# Sheet2.net
KiCad netlist of a schematic drawn in Altium Designer
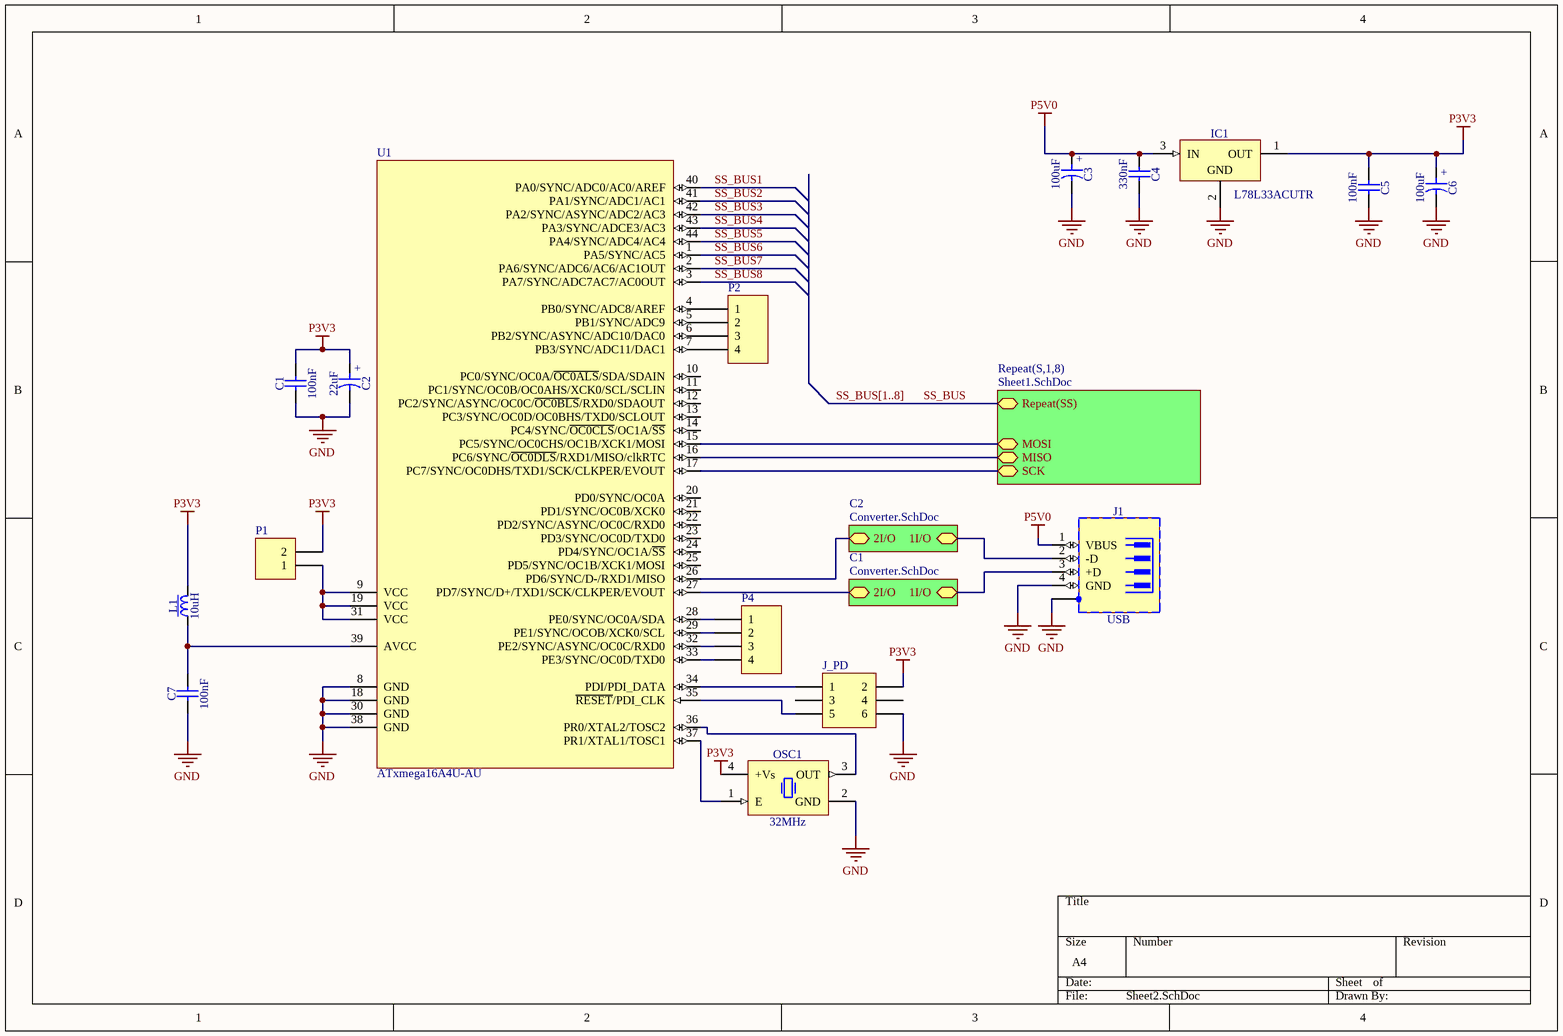
[diagram p0: Sheet2.SchDoc]

(export (version "E")
  (design (tool "Eeschema 10.0.6"))
  (components
    (comp (ref "C1")
      (value "100nF")
      (footprint "CAPC2012X135N")
      (description "Non-polarised capacitor")
      (fields
        (field (name "PART NUMBER") "CC0805_100NF_50V_10%_X7R")
        (field (name "VOLTAGE") "50V")
        (field (name "AUTHOR") "CERN DEM JLC")
      )
      (libsource (lib "Capacitors") (part "Capacitor - non polarized"))
    )
    (comp (ref "C2")
      (value "22uF")
      (footprint "CAPAE430X540N")
      (description "Polarised capacitor")
      (fields
        (field (name "PART NUMBER") "CAE430-540_22UF_10V_20%")
        (field (name "VOLTAGE") "10V")
        (field (name "AUTHOR") "CERN DEM JLC")
      )
      (libsource (lib "Capacitors") (part "Capacitor - polarized"))
    )
    (comp (ref "C3")
      (value "100uF")
      (footprint "CAPAE660X540N")
      (description "Polarised capacitor")
      (fields
        (field (name "PART NUMBER") "CAE660-540_100UF_6.3V_20%")
        (field (name "VOLTAGE") "6.3V")
        (field (name "AUTHOR") "CERN DEM JLC")
      )
      (libsource (lib "Capacitors") (part "Capacitor - polarized"))
    )
    (comp (ref "C4")
      (value "330nF")
      (footprint "CAPC2012X135N")
      (description "Non-polarised capacitor")
      (fields
        (field (name "PART NUMBER") "CC0805_330NF_16V_10%_X7R")
        (field (name "VOLTAGE") "16V")
        (field (name "AUTHOR") "CERN DEM JLC")
      )
      (libsource (lib "Capacitors") (part "Capacitor - non polarized"))
    )
    (comp (ref "C5")
      (value "100nF")
      (footprint "CAPC2012X135N")
      (description "Non-polarised capacitor")
      (fields
        (field (name "PART NUMBER") "CC0805_100NF_50V_10%_X7R")
        (field (name "VOLTAGE") "50V")
        (field (name "AUTHOR") "CERN DEM JLC")
      )
      (libsource (lib "Capacitors") (part "Capacitor - non polarized"))
    )
    (comp (ref "C6")
      (value "100uF")
      (footprint "CAPAE660X540N")
      (description "Polarised capacitor")
      (fields
        (field (name "PART NUMBER") "CAE660-540_100UF_6.3V_20%")
        (field (name "VOLTAGE") "6.3V")
        (field (name "AUTHOR") "CERN DEM JLC")
      )
      (libsource (lib "Capacitors") (part "Capacitor - polarized"))
    )
    (comp (ref "C7")
      (value "100nF")
      (footprint "CAPC2012X135N")
      (description "Non-polarised capacitor")
      (fields
        (field (name "PART NUMBER") "CC0805_100NF_50V_10%_X7R")
        (field (name "VOLTAGE") "50V")
        (field (name "AUTHOR") "CERN DEM JLC")
      )
      (libsource (lib "Capacitors") (part "Capacitor - non polarized"))
    )
    (comp (ref "IC1")
      (value "L78L33ACUTR")
      (footprint "SOT89")
      (description "3-Terminal Regulator 1=OUT 2=GND 3=IN")
      (fields (field (name "MANUFACTURER") "ST MICROELECTRONICS") (field (name "AUTHOR") "CERN DEM JLC"))
      (libsource (lib "ICs And Semiconductors") (part "REG3 1OUT-2GND-3IN"))
    )
    (comp (ref "J1")
      (value "USB")
      (footprint "FCI_87520-0010BLF")
      (description "4 Pin + 1 Shield USB Receptacle")
      (fields
        (field (name "PART NUMBER") "FCI_87520-0010BLF")
        (field (name "MANUFACTURER") "FCI")
        (field (name "AUTHOR") "CERN DEM JMW")
      )
      (libsource (lib "Connectors") (part "Connector USB 4 Pin + 1Shield"))
    )
    (comp (ref "J_PD")
      (value "~")
      (footprint "HDR2X3")
      (description "Header, 3-Pin, Dual row")
      (fields (field (name "PUBLISHER") "Altium Limited"))
      (libsource (lib "Miscellaneous Connectors") (part "Header 3X2"))
    )
    (comp (ref "L1")
      (value "10uH")
      (footprint "IND_MURATA_LQH32")
      (description "Inductor With Core")
      (fields
        (field (name "PART NUMBER") "IND_10UH_10%_MURATA_LQH32CN100K33L")
        (field (name "POWER") "450mA")
        (field (name "AUTHOR") "CERN DEM JLC")
      )
      (libsource (lib "Inductors & Transformers") (part "Inductor With Magnetic core"))
    )
    (comp (ref "OSC1")
      (value "32MHz")
      (footprint "OSC_IQD_CFPS-32")
      (description "Oscillator 4 pins 1=E 2=GND 3=OUT 4=+Vs")
      (fields
        (field (name "PART NUMBER") "OSC_32MHZ_IQD_LFSPXO025916")
        (field (name "MANUFACTURER") "IQD FREQUENCY PRODUCTS")
        (field (name "AUTHOR") "CERN DEM JLC")
      )
      (libsource (lib "ICs And Semiconductors") (part "Oscillator 1E 2GND 3OUT 4Vs"))
    )
    (comp (ref "P1")
      (value "~")
      (footprint "HDR1X2")
      (description "Header, 2-Pin")
      (fields (field (name "PUBLISHER") "Altium Limited"))
      (libsource (lib "Miscellaneous Connectors") (part "Header 2"))
    )
    (comp (ref "P2")
      (value "~")
      (footprint "HDR1X4")
      (description "Header, 4-Pin")
      (fields (field (name "PUBLISHER") "Altium Limited"))
      (libsource (lib "Miscellaneous Connectors") (part "Header 4"))
    )
    (comp (ref "P4")
      (value "~")
      (footprint "HDR1X4")
      (description "Header, 4-Pin")
      (fields (field (name "PUBLISHER") "Altium Limited"))
      (libsource (lib "Miscellaneous Connectors") (part "Header 4"))
    )
    (comp (ref "U1")
      (value "ATxmega16A4U-AU")
      (footprint "44A_N")
      (fields (field (name "PUBLISHER") "Altium Limited"))
      (libsource (lib "RFID_system_atxmegau") (part "ATxmega16A4-AU"))
    )
  )
  (nets
    (net (code "1") (name "/1I{slash}O") (class "Default")
      (node (ref "J1") (pin "3") (pinfunction "+D_3") (pintype "bidirectional"))
    )
    (net (code "2") (name "/1I{slash}O_1") (class "Default")
      (node (ref "J1") (pin "2") (pinfunction "-D_2") (pintype "bidirectional"))
    )
    (net (code "3") (name "/2I{slash}O") (class "Default")
      (node (ref "U1") (pin "27") (pinfunction "PD7/SYNC/D+/TXD1/SCK/CLKPER/EVOUT_27") (pintype "bidirectional"))
    )
    (net (code "4") (name "/2I{slash}O_1") (class "Default")
      (node (ref "U1") (pin "26") (pinfunction "PD6/SYNC/D-/RXD1/MISO_26") (pintype "bidirectional"))
    )
    (net (code "5") (name "/MISO") (class "Default")
      (node (ref "U1") (pin "16") (pinfunction "PC6/SYNC/~{OC0DLS}/RXD1/MISO/clkRTC_16") (pintype "bidirectional"))
    )
    (net (code "6") (name "/MOSI") (class "Default")
      (node (ref "U1") (pin "15") (pinfunction "PC5/SYNC/OC0CHS/OC1B/XCK1/MOSI_15") (pintype "bidirectional"))
    )
    (net (code "7") (name "/SCK") (class "Default")
      (node (ref "U1") (pin "17") (pinfunction "PC7/SYNC/OC0DHS/TXD1/SCK/CLKPER/EVOUT_17") (pintype "bidirectional"))
    )
    (net (code "9") (name "/SS_BUS1") (class "Default")
      (node (ref "U1") (pin "40") (pinfunction "PA0/SYNC/ADC0/AC0/AREF_40") (pintype "bidirectional"))
    )
    (net (code "10") (name "/SS_BUS2") (class "Default")
      (node (ref "U1") (pin "41") (pinfunction "PA1/SYNC/ADC1/AC1_41") (pintype "bidirectional"))
    )
    (net (code "11") (name "/SS_BUS3") (class "Default")
      (node (ref "U1") (pin "42") (pinfunction "PA2/SYNC/ASYNC/ADC2/AC3_42") (pintype "bidirectional"))
    )
    (net (code "12") (name "/SS_BUS4") (class "Default")
      (node (ref "U1") (pin "43") (pinfunction "PA3/SYNC/ADCE3/AC3_43") (pintype "bidirectional"))
    )
    (net (code "13") (name "/SS_BUS5") (class "Default")
      (node (ref "U1") (pin "44") (pinfunction "PA4/SYNC/ADC4/AC4_44") (pintype "bidirectional"))
    )
    (net (code "14") (name "/SS_BUS6") (class "Default")
      (node (ref "U1") (pin "1") (pinfunction "PA5/SYNC/AC5_1") (pintype "bidirectional"))
    )
    (net (code "15") (name "/SS_BUS7") (class "Default")
      (node (ref "U1") (pin "2") (pinfunction "PA6/SYNC/ADC6/AC6/AC1OUT_2") (pintype "bidirectional"))
    )
    (net (code "16") (name "/SS_BUS8") (class "Default")
      (node (ref "U1") (pin "3") (pinfunction "PA7/SYNC/ADC7AC7/AC0OUT_3") (pintype "bidirectional"))
    )
    (net (code "18") (name "GND") (class "Default")
      (node (ref "C1") (pin "1") (pinfunction "1_1") (pintype "passive"))
      (node (ref "C2") (pin "2") (pinfunction "2_2") (pintype "passive"))
      (node (ref "C3") (pin "2") (pinfunction "2_2") (pintype "passive"))
      (node (ref "C4") (pin "2") (pinfunction "2_2") (pintype "passive"))
      (node (ref "C5") (pin "2") (pinfunction "2_2") (pintype "passive"))
      (node (ref "C6") (pin "2") (pinfunction "2_2") (pintype "passive"))
      (node (ref "C7") (pin "1") (pinfunction "1_1") (pintype "passive"))
      (node (ref "IC1") (pin "2") (pinfunction "GND_2") (pintype "power_in"))
      (node (ref "J1") (pin "4") (pinfunction "GND_4") (pintype "bidirectional"))
      (node (ref "J1") (pin "5") (pinfunction "SHIELD_5") (pintype "power_in"))
      (node (ref "J_PD") (pin "6") (pinfunction "6_6") (pintype "passive"))
      (node (ref "OSC1") (pin "2") (pinfunction "GND_2") (pintype "power_in"))
      (node (ref "U1") (pin "18") (pinfunction "GND_18") (pintype "power_in"))
      (node (ref "U1") (pin "30") (pinfunction "GND_30") (pintype "power_in"))
      (node (ref "U1") (pin "38") (pinfunction "GND_38") (pintype "power_in"))
      (node (ref "U1") (pin "8") (pinfunction "GND_8") (pintype "power_in"))
    )
    (net (code "19") (name "Net-(OSC1-E)") (class "Default")
      (node (ref "OSC1") (pin "1") (pinfunction "E_1") (pintype "input"))
      (node (ref "U1") (pin "37") (pinfunction "PR1/XTAL1/TOSC1_37") (pintype "bidirectional"))
    )
    (net (code "20") (name "Net-(OSC1-OUT)") (class "Default")
      (node (ref "OSC1") (pin "3") (pinfunction "OUT_3") (pintype "output"))
      (node (ref "U1") (pin "36") (pinfunction "PR0/XTAL2/TOSC2_36") (pintype "bidirectional"))
    )
    (net (code "21") (name "Net-(P1-Pad1)") (class "Default")
      (node (ref "P1") (pin "1") (pinfunction "1_1") (pintype "passive"))
      (node (ref "U1") (pin "19") (pinfunction "VCC_19") (pintype "power_in"))
      (node (ref "U1") (pin "31") (pinfunction "VCC_31") (pintype "power_in"))
      (node (ref "U1") (pin "9") (pinfunction "VCC_9") (pintype "power_in"))
    )
    (net (code "22") (name "Net-(U1-AVCC)") (class "Default")
      (node (ref "C7") (pin "2") (pinfunction "2_2") (pintype "passive"))
      (node (ref "L1") (pin "1") (pinfunction "1_1") (pintype "passive"))
      (node (ref "U1") (pin "39") (pinfunction "AVCC_39") (pintype "power_in"))
    )
    (net (code "23") (name "Net-(U1-PB0{slash}SYNC{slash}ADC8{slash}AREF)") (class "Default")
      (node (ref "P2") (pin "1") (pinfunction "1_1") (pintype "passive"))
      (node (ref "U1") (pin "4") (pinfunction "PB0/SYNC/ADC8/AREF_4") (pintype "bidirectional"))
    )
    (net (code "24") (name "Net-(U1-PB1{slash}SYNC{slash}ADC9)") (class "Default")
      (node (ref "P2") (pin "2") (pinfunction "2_2") (pintype "passive"))
      (node (ref "U1") (pin "5") (pinfunction "PB1/SYNC/ADC9_5") (pintype "bidirectional"))
    )
    (net (code "25") (name "Net-(U1-PB2{slash}SYNC{slash}ASYNC{slash}ADC10{slash}DAC0)") (class "Default")
      (node (ref "P2") (pin "3") (pinfunction "3_3") (pintype "passive"))
      (node (ref "U1") (pin "6") (pinfunction "PB2/SYNC/ASYNC/ADC10/DAC0_6") (pintype "bidirectional"))
    )
    (net (code "26") (name "Net-(U1-PB3{slash}SYNC{slash}ADC11{slash}DAC1)") (class "Default")
      (node (ref "P2") (pin "4") (pinfunction "4_4") (pintype "passive"))
      (node (ref "U1") (pin "7") (pinfunction "PB3/SYNC/ADC11/DAC1_7") (pintype "bidirectional"))
    )
    (net (code "27") (name "Net-(U1-PDI{slash}PDI_DATA)") (class "Default")
      (node (ref "J_PD") (pin "1") (pinfunction "1_1") (pintype "passive"))
      (node (ref "U1") (pin "34") (pinfunction "PDI/PDI_DATA_34") (pintype "bidirectional"))
    )
    (net (code "28") (name "Net-(U1-PE0{slash}SYNC{slash}OC0A{slash}SDA)") (class "Default")
      (node (ref "P4") (pin "1") (pinfunction "1_1") (pintype "passive"))
      (node (ref "U1") (pin "28") (pinfunction "PE0/SYNC/OC0A/SDA_28") (pintype "bidirectional"))
    )
    (net (code "29") (name "Net-(U1-PE1{slash}SYNC{slash}OCOB{slash}XCK0{slash}SCL)") (class "Default")
      (node (ref "P4") (pin "2") (pinfunction "2_2") (pintype "passive"))
      (node (ref "U1") (pin "29") (pinfunction "PE1/SYNC/OCOB/XCK0/SCL_29") (pintype "bidirectional"))
    )
    (net (code "30") (name "Net-(U1-PE2{slash}SYNC{slash}ASYNC{slash}OC0C{slash}RXD0)") (class "Default")
      (node (ref "P4") (pin "3") (pinfunction "3_3") (pintype "passive"))
      (node (ref "U1") (pin "32") (pinfunction "PE2/SYNC/ASYNC/OC0C/RXD0_32") (pintype "bidirectional"))
    )
    (net (code "31") (name "Net-(U1-PE3{slash}SYNC{slash}OC0D{slash}TXD0)") (class "Default")
      (node (ref "P4") (pin "4") (pinfunction "4_4") (pintype "passive"))
      (node (ref "U1") (pin "33") (pinfunction "PE3/SYNC/OC0D/TXD0_33") (pintype "bidirectional"))
    )
    (net (code "32") (name "Net-(U1-~{RESET}{slash}PDI_CLK)") (class "Default")
      (node (ref "J_PD") (pin "5") (pinfunction "5_5") (pintype "passive"))
      (node (ref "U1") (pin "35") (pinfunction "~{RESET}/PDI_CLK_35") (pintype "input"))
    )
    (net (code "33") (name "P3V3") (class "Default")
      (node (ref "C1") (pin "2") (pinfunction "2_2") (pintype "passive"))
      (node (ref "C2") (pin "1") (pinfunction "1_1") (pintype "passive"))
      (node (ref "C5") (pin "1") (pinfunction "1_1") (pintype "passive"))
      (node (ref "C6") (pin "1") (pinfunction "1_1") (pintype "passive"))
      (node (ref "IC1") (pin "1") (pinfunction "OUT_1") (pintype "power_in"))
      (node (ref "J_PD") (pin "2") (pinfunction "2_2") (pintype "passive"))
      (node (ref "L1") (pin "2") (pinfunction "2_2") (pintype "passive"))
      (node (ref "OSC1") (pin "4") (pinfunction "+Vs_4") (pintype "power_in"))
      (node (ref "P1") (pin "2") (pinfunction "2_2") (pintype "passive"))
    )
    (net (code "34") (name "P5V0") (class "Default")
      (node (ref "C3") (pin "1") (pinfunction "1_1") (pintype "passive"))
      (node (ref "C4") (pin "1") (pinfunction "1_1") (pintype "passive"))
      (node (ref "IC1") (pin "3") (pinfunction "IN_3") (pintype "input"))
      (node (ref "J1") (pin "1") (pinfunction "VBUS_1") (pintype "bidirectional"))
    )
    (net (code "35") (name "unconnected-(J_PD-Pad3)") (class "Default")
      (node (ref "J_PD") (pin "3") (pinfunction "3_3") (pintype "passive"))
    )
    (net (code "36") (name "unconnected-(J_PD-Pad4)") (class "Default")
      (node (ref "J_PD") (pin "4") (pinfunction "4_4") (pintype "passive"))
    )
    (net (code "37") (name "unconnected-(U1-PC0{slash}SYNC{slash}OC0A{slash}~{OC0ALS}{slash}SDA{slash}SDAIN-Pad10)") (class "Default")
      (node (ref "U1") (pin "10") (pinfunction "PC0/SYNC/OC0A/~{OC0ALS}/SDA/SDAIN_10") (pintype "bidirectional"))
    )
    (net (code "38") (name "unconnected-(U1-PC1{slash}SYNC{slash}OC0B{slash}OC0AHS{slash}XCK0{slash}SCL{slash}SCLIN-Pad11)") (class "Default")
      (node (ref "U1") (pin "11") (pinfunction "PC1/SYNC/OC0B/OC0AHS/XCK0/SCL/SCLIN_11") (pintype "bidirectional"))
    )
    (net (code "39") (name "unconnected-(U1-PC2{slash}SYNC{slash}ASYNC{slash}OC0C{slash}~{OC0BLS}{slash}RXD0{slash}SDAOUT-Pad12)") (class "Default")
      (node (ref "U1") (pin "12") (pinfunction "PC2/SYNC/ASYNC/OC0C/~{OC0BLS}/RXD0/SDAOUT_12") (pintype "bidirectional"))
    )
    (net (code "40") (name "unconnected-(U1-PC3{slash}SYNC{slash}OC0D{slash}OC0BHS{slash}TXD0{slash}SCLOUT-Pad13)") (class "Default")
      (node (ref "U1") (pin "13") (pinfunction "PC3/SYNC/OC0D/OC0BHS/TXD0/SCLOUT_13") (pintype "bidirectional"))
    )
    (net (code "41") (name "unconnected-(U1-PC4{slash}SYNC{slash}~{OC0CLS}{slash}OC1A{slash}~{SS}-Pad14)") (class "Default")
      (node (ref "U1") (pin "14") (pinfunction "PC4/SYNC/~{OC0CLS}/OC1A/~{SS}_14") (pintype "bidirectional"))
    )
    (net (code "42") (name "unconnected-(U1-PD0{slash}SYNC{slash}OC0A-Pad20)") (class "Default")
      (node (ref "U1") (pin "20") (pinfunction "PD0/SYNC/OC0A_20") (pintype "bidirectional"))
    )
    (net (code "43") (name "unconnected-(U1-PD1{slash}SYNC{slash}OC0B{slash}XCK0-Pad21)") (class "Default")
      (node (ref "U1") (pin "21") (pinfunction "PD1/SYNC/OC0B/XCK0_21") (pintype "bidirectional"))
    )
    (net (code "44") (name "unconnected-(U1-PD2{slash}SYNC{slash}ASYNC{slash}OC0C{slash}RXD0-Pad22)") (class "Default")
      (node (ref "U1") (pin "22") (pinfunction "PD2/SYNC/ASYNC/OC0C/RXD0_22") (pintype "bidirectional"))
    )
    (net (code "45") (name "unconnected-(U1-PD3{slash}SYNC{slash}OC0D{slash}TXD0-Pad23)") (class "Default")
      (node (ref "U1") (pin "23") (pinfunction "PD3/SYNC/OC0D/TXD0_23") (pintype "bidirectional"))
    )
    (net (code "46") (name "unconnected-(U1-PD4{slash}SYNC{slash}OC1A{slash}~{SS}-Pad24)") (class "Default")
      (node (ref "U1") (pin "24") (pinfunction "PD4/SYNC/OC1A/~{SS}_24") (pintype "bidirectional"))
    )
    (net (code "47") (name "unconnected-(U1-PD5{slash}SYNC{slash}OC1B{slash}XCK1{slash}MOSI-Pad25)") (class "Default")
      (node (ref "U1") (pin "25") (pinfunction "PD5/SYNC/OC1B/XCK1/MOSI_25") (pintype "bidirectional"))
    )
  )
)
